# 04_Sensors_IO.net
KiCad netlist of a schematic drawn in Altium Designer
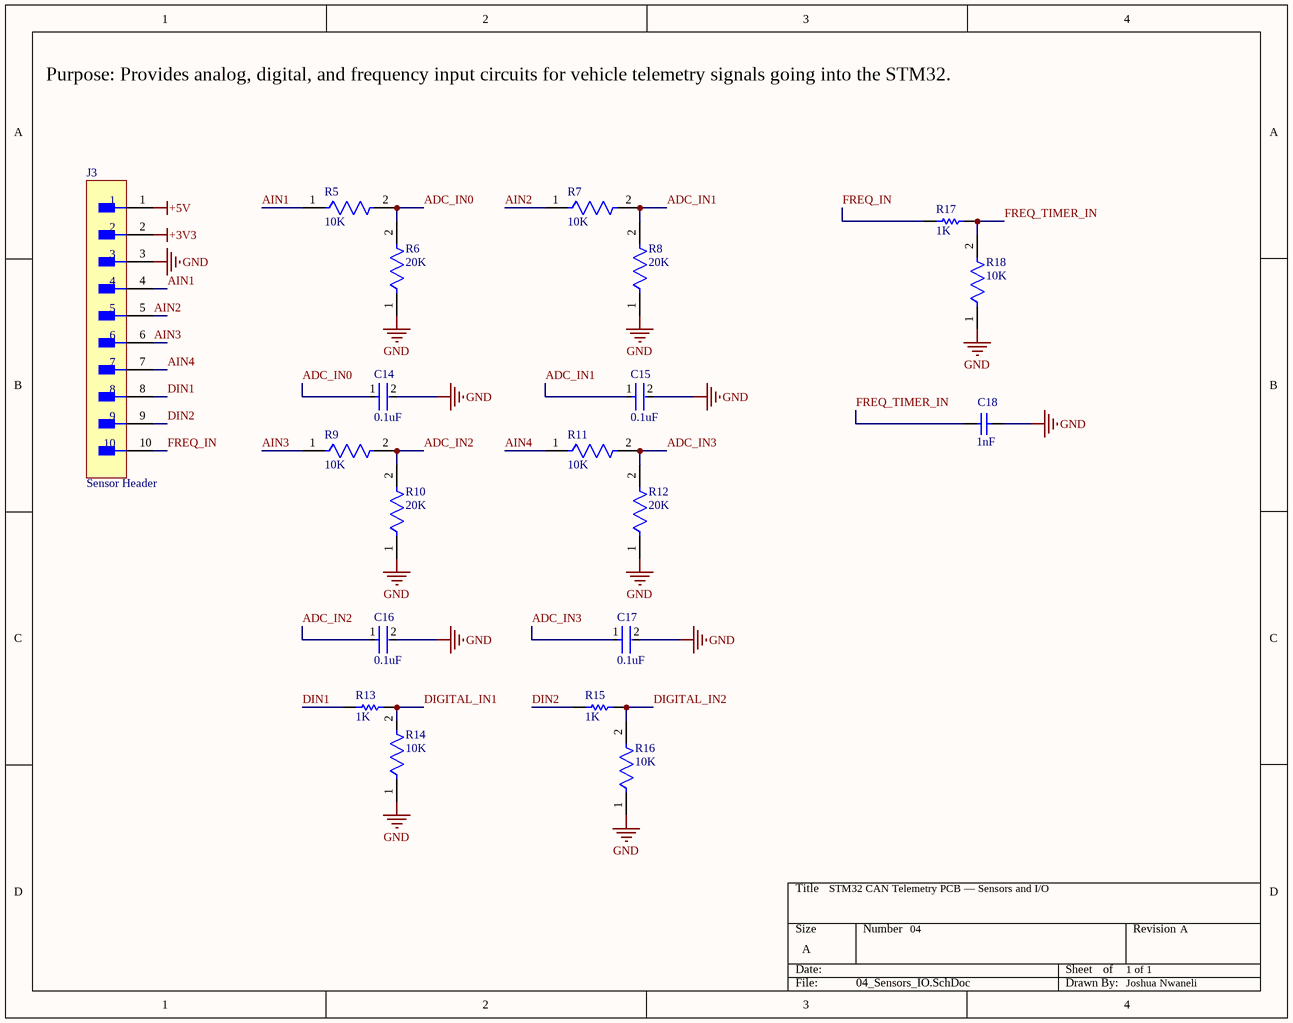
[diagram p0: 04_Sensors_IO.SchDoc]

(export (version "E")
  (design (tool "Eeschema 10.0.6"))
  (components
    (comp (ref "C14")
      (value "0.1uF")
      (footprint "FP-CC0805-EB-MFG")
      (description "CC0805KKX7RYBB104 Capacitor Ceramic 0.01uF 250V X7R 10% 0805 T/R")
      (fields (field (name "TOLERANCE") "10%"))
      (libsource (lib "Altium Content Vault") (part "b4654b650e69147ec39a6b967a45e02"))
    )
    (comp (ref "C15")
      (value "0.1uF")
      (footprint "FP-CC0805-EB-MFG")
      (description "CC0805KKX7RYBB104 Capacitor Ceramic 0.01uF 250V X7R 10% 0805 T/R")
      (fields (field (name "TOLERANCE") "10%"))
      (libsource (lib "Altium Content Vault") (part "b4654b650e69147ec39a6b967a45e02"))
    )
    (comp (ref "C16")
      (value "0.1uF")
      (footprint "FP-CC0805-EB-MFG")
      (description "CC0805KKX7RYBB104 Capacitor Ceramic 0.01uF 250V X7R 10% 0805 T/R")
      (fields (field (name "TOLERANCE") "10%"))
      (libsource (lib "Altium Content Vault") (part "b4654b650e69147ec39a6b967a45e02"))
    )
    (comp (ref "C17")
      (value "0.1uF")
      (footprint "FP-CC0805-EB-MFG")
      (description "CC0805KKX7RYBB104 Capacitor Ceramic 0.01uF 250V X7R 10% 0805 T/R")
      (fields (field (name "TOLERANCE") "10%"))
      (libsource (lib "Altium Content Vault") (part "b4654b650e69147ec39a6b967a45e02"))
    )
    (comp (ref "C18")
      (value "1nF")
      (footprint "CAPC2013X127X50NL20T25")
      (fields
        (field (name "PART NUMBER") "08052C102MAT2A")
        (field (name "MANUFACTURER") "AVX Interconnect / Elco")
      )
      (libsource (lib "Altium Content Vault") (part "CAP"))
    )
    (comp (ref "J3")
      (value "Sensor Header")
      (footprint "FP-TSW-110-07-T-S-MFG")
      (description "TSW-110-07-T-S TSW - Samtec 2.54mm Pin Header 10.92mm Overall Pin Length (07) (mcv)(TO22)")
      (libsource (lib "Altium Content Vault") (part "TSW-110-07-T-S"))
    )
    (comp (ref "R5")
      (value "10K")
      (footprint "FP-CRGP0805-IPC_C")
      (description "CRGP 0805 10K 1%")
      (fields (field (name "MANUFACTURER PART NUMBER") "CRGP0805F10K") (field (name "MANUFACTURER") "TE"))
      (libsource (lib "Altium Content Vault") (part "1029c3af85768c4190bb7ad29bc67b5"))
    )
    (comp (ref "R6")
      (value "20K")
      (footprint "FP-RN732A-MFG")
      (description "SMD Chip Resistor, Thin Film, 20KΩ, 100 V, 0805 [2012 Metric], 100 mW, 0.1%, RN73 Series")
      (fields
        (field (name "MANUFACTURER") "TE Connectivity")
        (field (name "OCTOPART") "https://octopart.com/rn73c2a20kbtdf-te+connectivity-21411984")
      )
      (libsource (lib "Altium Content Vault") (part "1029c3af85768c4190bb7ad29bc67b5"))
    )
    (comp (ref "R7")
      (value "10K")
      (footprint "FP-CRGP0805-IPC_C")
      (description "CRGP 0805 10K 1%")
      (fields (field (name "MANUFACTURER PART NUMBER") "CRGP0805F10K") (field (name "MANUFACTURER") "TE"))
      (libsource (lib "Altium Content Vault") (part "1029c3af85768c4190bb7ad29bc67b5"))
    )
    (comp (ref "R8")
      (value "20K")
      (footprint "FP-RN732A-MFG")
      (description "SMD Chip Resistor, Thin Film, 20KΩ, 100 V, 0805 [2012 Metric], 100 mW, 0.1%, RN73 Series")
      (fields
        (field (name "MANUFACTURER") "TE Connectivity")
        (field (name "OCTOPART") "https://octopart.com/rn73c2a20kbtdf-te+connectivity-21411984")
      )
      (libsource (lib "Altium Content Vault") (part "1029c3af85768c4190bb7ad29bc67b5"))
    )
    (comp (ref "R9")
      (value "10K")
      (footprint "FP-CRGP0805-IPC_C")
      (description "CRGP 0805 10K 1%")
      (fields (field (name "MANUFACTURER PART NUMBER") "CRGP0805F10K") (field (name "MANUFACTURER") "TE"))
      (libsource (lib "Altium Content Vault") (part "1029c3af85768c4190bb7ad29bc67b5"))
    )
    (comp (ref "R10")
      (value "20K")
      (footprint "FP-RN732A-MFG")
      (description "SMD Chip Resistor, Thin Film, 20KΩ, 100 V, 0805 [2012 Metric], 100 mW, 0.1%, RN73 Series")
      (fields
        (field (name "MANUFACTURER") "TE Connectivity")
        (field (name "OCTOPART") "https://octopart.com/rn73c2a20kbtdf-te+connectivity-21411984")
      )
      (libsource (lib "Altium Content Vault") (part "1029c3af85768c4190bb7ad29bc67b5"))
    )
    (comp (ref "R11")
      (value "10K")
      (footprint "FP-CRGP0805-IPC_C")
      (description "CRGP 0805 10K 1%")
      (fields (field (name "MANUFACTURER PART NUMBER") "CRGP0805F10K") (field (name "MANUFACTURER") "TE"))
      (libsource (lib "Altium Content Vault") (part "1029c3af85768c4190bb7ad29bc67b5"))
    )
    (comp (ref "R12")
      (value "20K")
      (footprint "FP-RN732A-MFG")
      (description "SMD Chip Resistor, Thin Film, 20KΩ, 100 V, 0805 [2012 Metric], 100 mW, 0.1%, RN73 Series")
      (fields
        (field (name "MANUFACTURER") "TE Connectivity")
        (field (name "OCTOPART") "https://octopart.com/rn73c2a20kbtdf-te+connectivity-21411984")
      )
      (libsource (lib "Altium Content Vault") (part "1029c3af85768c4190bb7ad29bc67b5"))
    )
    (comp (ref "R13")
      (value "1K")
      (footprint "RESC2013X50X30ML20T20")
      (fields (field (name "MANUFACTURER") "Vishay Dale") (field (name "PART NUMBER") "CRCW08051K00FKTC"))
      (libsource (lib "Altium Content Vault") (part "RES"))
    )
    (comp (ref "R14")
      (value "10K")
      (footprint "FP-CRGP0805-IPC_C")
      (description "CRGP 0805 10K 1%")
      (fields (field (name "MANUFACTURER PART NUMBER") "CRGP0805F10K") (field (name "MANUFACTURER") "TE"))
      (libsource (lib "Altium Content Vault") (part "1029c3af85768c4190bb7ad29bc67b5"))
    )
    (comp (ref "R15")
      (value "1K")
      (footprint "RESC2013X50X30ML20T20")
      (fields (field (name "MANUFACTURER") "Vishay Dale") (field (name "PART NUMBER") "CRCW08051K00FKTC"))
      (libsource (lib "Altium Content Vault") (part "RES"))
    )
    (comp (ref "R16")
      (value "10K")
      (footprint "FP-CRGP0805-IPC_C")
      (description "CRGP 0805 10K 1%")
      (fields (field (name "MANUFACTURER PART NUMBER") "CRGP0805F10K") (field (name "MANUFACTURER") "TE"))
      (libsource (lib "Altium Content Vault") (part "1029c3af85768c4190bb7ad29bc67b5"))
    )
    (comp (ref "R17")
      (value "1K")
      (footprint "RESC2013X50X30ML20T20")
      (fields (field (name "MANUFACTURER") "Vishay Dale") (field (name "PART NUMBER") "CRCW08051K00FKTC"))
      (libsource (lib "Altium Content Vault") (part "RES"))
    )
    (comp (ref "R18")
      (value "10K")
      (footprint "FP-CRGP0805-IPC_C")
      (description "CRGP 0805 10K 1%")
      (fields (field (name "MANUFACTURER PART NUMBER") "CRGP0805F10K") (field (name "MANUFACTURER") "TE"))
      (libsource (lib "Altium Content Vault") (part "1029c3af85768c4190bb7ad29bc67b5"))
    )
  )
  (nets
    (net (code "1") (name "+3V3") (class "Default")
      (node (ref "J3") (pin "2") (pinfunction "2_2") (pintype "passive"))
    )
    (net (code "2") (name "+5V") (class "Default")
      (node (ref "J3") (pin "1") (pinfunction "1_1") (pintype "passive"))
    )
    (net (code "3") (name "/ADC_IN0") (class "Default")
      (node (ref "C14") (pin "1") (pinfunction "1_1") (pintype "passive"))
      (node (ref "R5") (pin "2") (pinfunction "2_2") (pintype "passive"))
      (node (ref "R6") (pin "2") (pinfunction "2_2") (pintype "passive"))
    )
    (net (code "4") (name "/ADC_IN1") (class "Default")
      (node (ref "C15") (pin "1") (pinfunction "1_1") (pintype "passive"))
      (node (ref "R7") (pin "2") (pinfunction "2_2") (pintype "passive"))
      (node (ref "R8") (pin "2") (pinfunction "2_2") (pintype "passive"))
    )
    (net (code "5") (name "/ADC_IN2") (class "Default")
      (node (ref "C16") (pin "1") (pinfunction "1_1") (pintype "passive"))
      (node (ref "R10") (pin "2") (pinfunction "2_2") (pintype "passive"))
      (node (ref "R9") (pin "2") (pinfunction "2_2") (pintype "passive"))
    )
    (net (code "6") (name "/ADC_IN3") (class "Default")
      (node (ref "C17") (pin "1") (pinfunction "1_1") (pintype "passive"))
      (node (ref "R11") (pin "2") (pinfunction "2_2") (pintype "passive"))
      (node (ref "R12") (pin "2") (pinfunction "2_2") (pintype "passive"))
    )
    (net (code "7") (name "/AIN1") (class "Default")
      (node (ref "J3") (pin "4") (pinfunction "4_4") (pintype "passive"))
      (node (ref "R5") (pin "1") (pinfunction "1_1") (pintype "passive"))
    )
    (net (code "8") (name "/AIN2") (class "Default")
      (node (ref "J3") (pin "5") (pinfunction "5_5") (pintype "passive"))
      (node (ref "R7") (pin "1") (pinfunction "1_1") (pintype "passive"))
    )
    (net (code "9") (name "/AIN3") (class "Default")
      (node (ref "J3") (pin "6") (pinfunction "6_6") (pintype "passive"))
      (node (ref "R9") (pin "1") (pinfunction "1_1") (pintype "passive"))
    )
    (net (code "10") (name "/AIN4") (class "Default")
      (node (ref "J3") (pin "7") (pinfunction "7_7") (pintype "passive"))
      (node (ref "R11") (pin "1") (pinfunction "1_1") (pintype "passive"))
    )
    (net (code "11") (name "/DIGITAL_IN1") (class "Default")
      (node (ref "R13") (pin "2") (pinfunction "2_2") (pintype "passive"))
      (node (ref "R14") (pin "2") (pinfunction "2_2") (pintype "passive"))
    )
    (net (code "12") (name "/DIGITAL_IN2") (class "Default")
      (node (ref "R15") (pin "2") (pinfunction "2_2") (pintype "passive"))
      (node (ref "R16") (pin "2") (pinfunction "2_2") (pintype "passive"))
    )
    (net (code "13") (name "/DIN1") (class "Default")
      (node (ref "J3") (pin "8") (pinfunction "8_8") (pintype "passive"))
      (node (ref "R13") (pin "1") (pinfunction "1_1") (pintype "passive"))
    )
    (net (code "14") (name "/DIN2") (class "Default")
      (node (ref "J3") (pin "9") (pinfunction "9_9") (pintype "passive"))
      (node (ref "R15") (pin "1") (pinfunction "1_1") (pintype "passive"))
    )
    (net (code "15") (name "/FREQ_IN") (class "Default")
      (node (ref "J3") (pin "10") (pinfunction "10_10") (pintype "passive"))
      (node (ref "R17") (pin "1") (pinfunction "1_1") (pintype "passive"))
    )
    (net (code "16") (name "/FREQ_TIMER_IN") (class "Default")
      (node (ref "C18") (pin "1") (pinfunction "1_1") (pintype "passive"))
      (node (ref "R17") (pin "2") (pinfunction "2_2") (pintype "passive"))
      (node (ref "R18") (pin "2") (pinfunction "2_2") (pintype "passive"))
    )
    (net (code "17") (name "GND") (class "Default")
      (node (ref "C14") (pin "2") (pinfunction "2_2") (pintype "passive"))
      (node (ref "C15") (pin "2") (pinfunction "2_2") (pintype "passive"))
      (node (ref "C16") (pin "2") (pinfunction "2_2") (pintype "passive"))
      (node (ref "C17") (pin "2") (pinfunction "2_2") (pintype "passive"))
      (node (ref "C18") (pin "2") (pinfunction "2_2") (pintype "passive"))
      (node (ref "J3") (pin "3") (pinfunction "3_3") (pintype "passive"))
      (node (ref "R10") (pin "1") (pinfunction "1_1") (pintype "passive"))
      (node (ref "R12") (pin "1") (pinfunction "1_1") (pintype "passive"))
      (node (ref "R14") (pin "1") (pinfunction "1_1") (pintype "passive"))
      (node (ref "R16") (pin "1") (pinfunction "1_1") (pintype "passive"))
      (node (ref "R18") (pin "1") (pinfunction "1_1") (pintype "passive"))
      (node (ref "R6") (pin "1") (pinfunction "1_1") (pintype "passive"))
      (node (ref "R8") (pin "1") (pinfunction "1_1") (pintype "passive"))
    )
  )
)
